# Orone-mini-S8H-v0r001.net
KiCad netlist of a schematic drawn in EAGLE
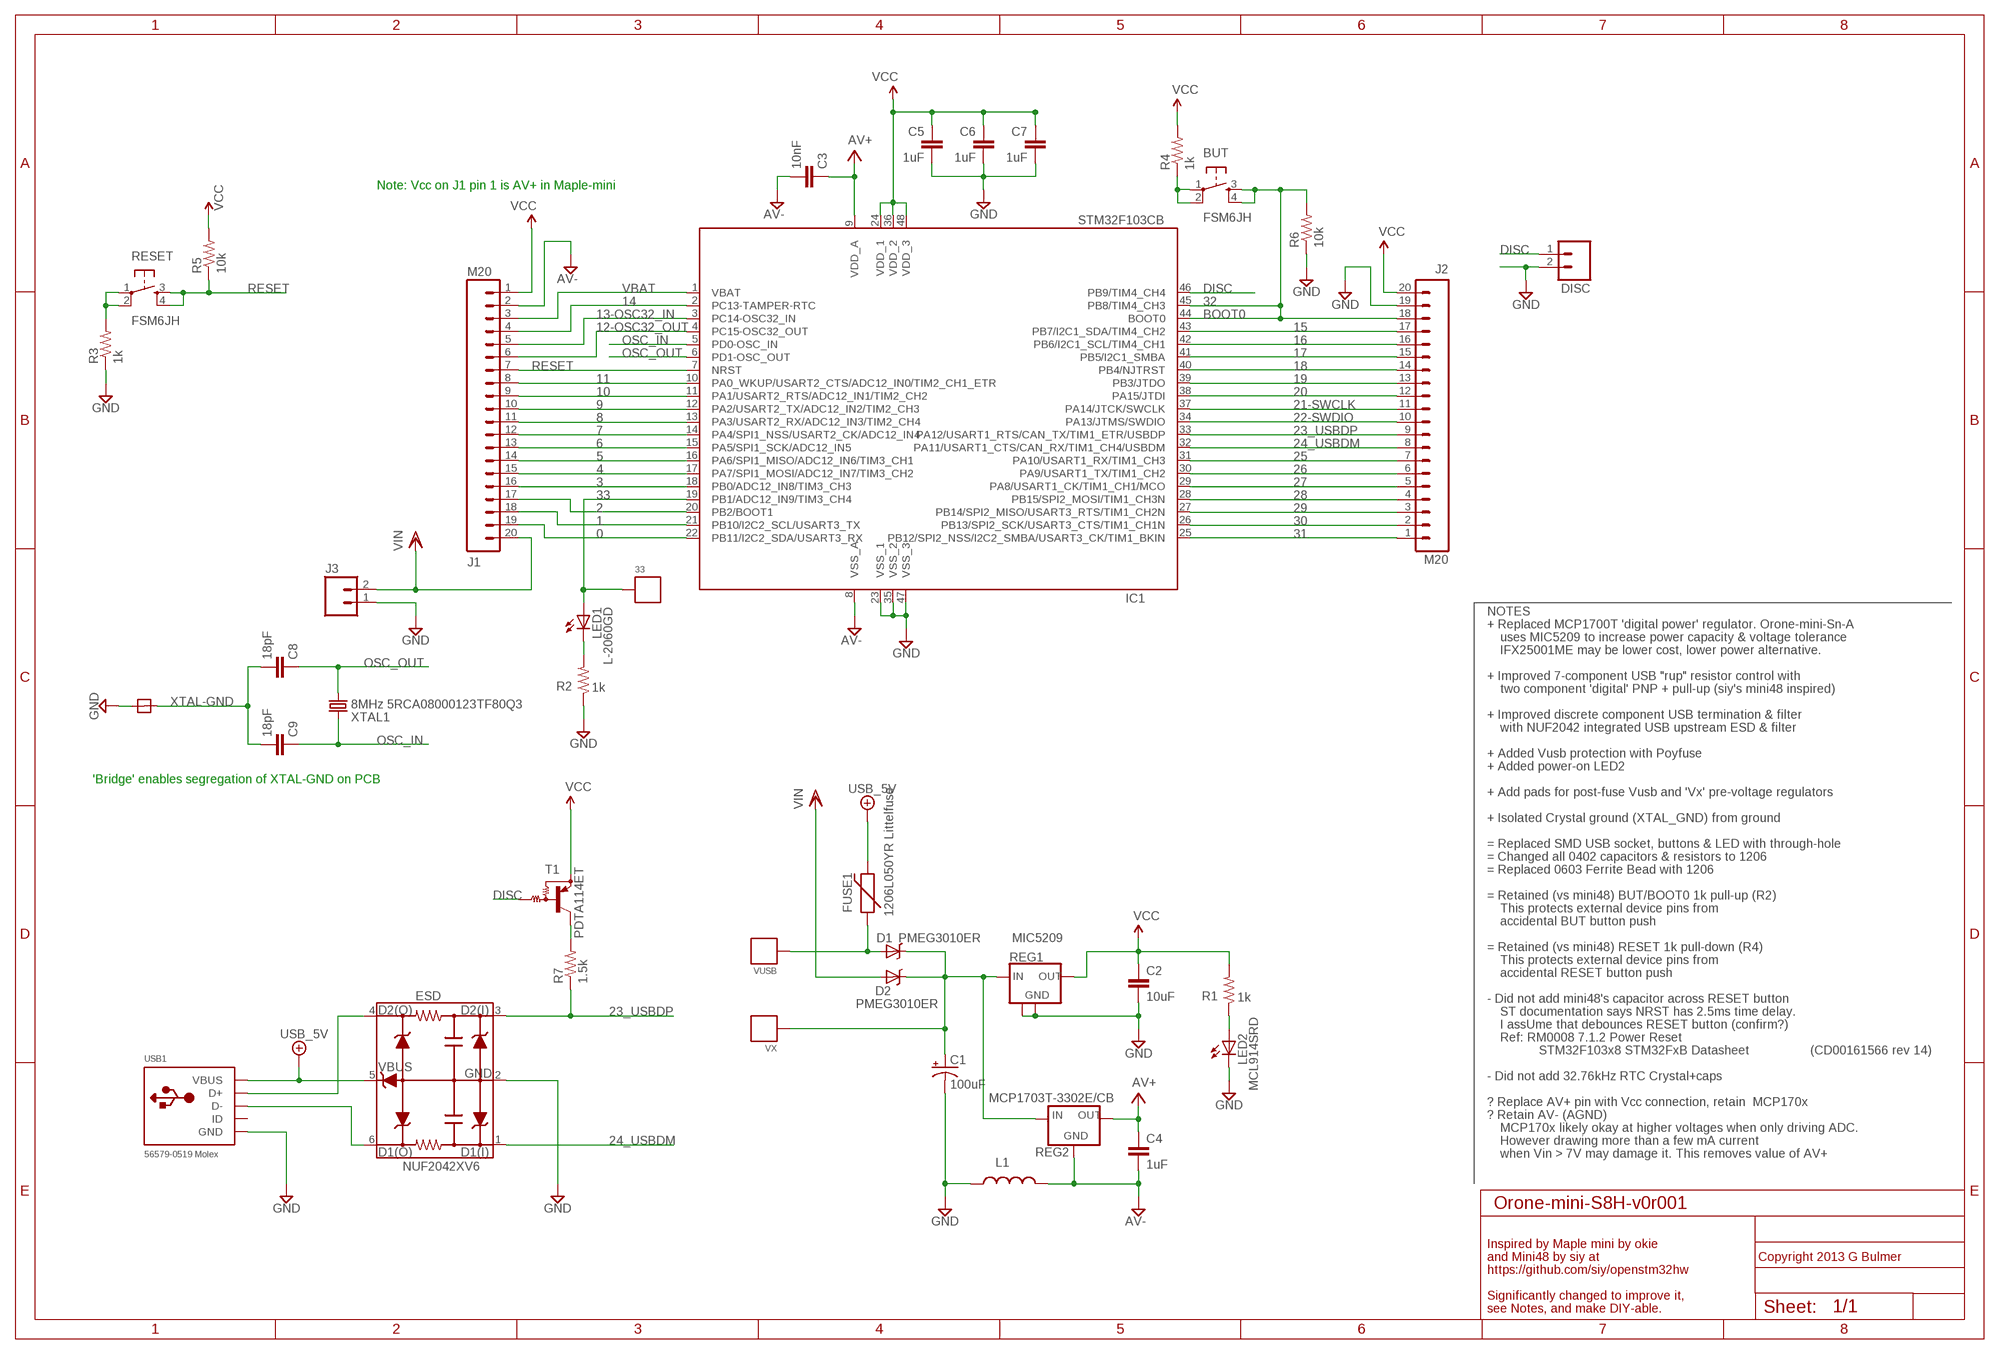
[diagram p0: schematic, sheet 1]

(export (version "E")
  (design (tool "Eeschema 10.0.6"))
  (components
    (comp (ref "33")
      (value "SIGNAL-PIN1")
      (footprint "eagle-import:1PIN")
      (libsource (lib "eagle-import") (part "SIGNAL-PIN1"))
    )
    (comp (ref "BUT")
      (value "FSM6JH")
      (footprint "eagle-import:TACTILE-PTH")
      (libsource (lib "eagle-import") (part "TAC_SWITCHPTH"))
    )
    (comp (ref "C1")
      (value "100uF")
      (footprint "eagle-import:EIA7343")
      (libsource (lib "eagle-import") (part "CAP_POL7343"))
    )
    (comp (ref "C2")
      (value "10uF")
      (footprint "eagle-import:1206")
      (libsource (lib "eagle-import") (part "CAP1206"))
    )
    (comp (ref "C3")
      (value "10nF")
      (footprint "eagle-import:1206")
      (libsource (lib "eagle-import") (part "CAP1206"))
    )
    (comp (ref "C4")
      (value "1uF")
      (footprint "eagle-import:1206")
      (libsource (lib "eagle-import") (part "CAP1206"))
    )
    (comp (ref "C5")
      (value "1uF")
      (footprint "eagle-import:1206")
      (libsource (lib "eagle-import") (part "CAP1206"))
    )
    (comp (ref "C6")
      (value "1uF")
      (footprint "eagle-import:1206")
      (libsource (lib "eagle-import") (part "CAP1206"))
    )
    (comp (ref "C7")
      (value "1uF")
      (footprint "eagle-import:1206")
      (libsource (lib "eagle-import") (part "CAP1206"))
    )
    (comp (ref "C8")
      (value "18pF")
      (footprint "eagle-import:1206")
      (libsource (lib "eagle-import") (part "CAP1206"))
    )
    (comp (ref "C9")
      (value "18pF")
      (footprint "eagle-import:1206")
      (libsource (lib "eagle-import") (part "CAP1206"))
    )
    (comp (ref "D1")
      (value "PMEG3010ER")
      (footprint "eagle-import:SOD-123W")
      (libsource (lib "eagle-import") (part "DIODE-SCHOTTKYSOD-123W"))
    )
    (comp (ref "D2")
      (value "PMEG3010ER")
      (footprint "eagle-import:SOD-123W")
      (libsource (lib "eagle-import") (part "DIODE-SCHOTTKYSOD-123W"))
    )
    (comp (ref "DISC")
      (value "M021X02_NO_SILK")
      (footprint "eagle-import:1X02_NO_SILK")
      (libsource (lib "eagle-import") (part "M021X02_NO_SILK"))
    )
    (comp (ref "ESD")
      (value "NUF2042XV6")
      (footprint "eagle-import:SOT563")
      (libsource (lib "eagle-import") (part "NUF2042XV6SOT563"))
    )
    (comp (ref "FUSE1")
      (value "1206L050YR Littelfuse")
      (footprint "eagle-import:PTC-1206")
      (libsource (lib "eagle-import") (part "PTCSMD"))
    )
    (comp (ref "IC1")
      (value "STM32F103CB")
      (footprint "eagle-import:LQFP48")
      (libsource (lib "eagle-import") (part "STM32F103CB"))
    )
    (comp (ref "J1")
      (value "M20")
      (footprint "eagle-import:1X20")
      (libsource (lib "eagle-import") (part "M20"))
    )
    (comp (ref "J2")
      (value "M20")
      (footprint "eagle-import:1X20")
      (libsource (lib "eagle-import") (part "M20"))
    )
    (comp (ref "J3")
      (value "M02POLAR")
      (footprint "eagle-import:MOLEX-1X2")
      (libsource (lib "eagle-import") (part "M02POLAR"))
    )
    (comp (ref "L1")
      (value "INDUCTOR1206")
      (footprint "eagle-import:1206")
      (libsource (lib "eagle-import") (part "INDUCTOR1206"))
    )
    (comp (ref "LED1")
      (value "L-2060GD")
      (footprint "eagle-import:LED1.8MM-1MM")
      (libsource (lib "eagle-import") (part "LED1.8MM-1MM"))
    )
    (comp (ref "LED2")
      (value "MCL914SRD")
      (footprint "eagle-import:LED1.8MM-1MM")
      (libsource (lib "eagle-import") (part "LED1.8MM-1MM"))
    )
    (comp (ref "R1")
      (value "1k")
      (footprint "eagle-import:1206")
      (libsource (lib "eagle-import") (part "RESISTOR1206"))
    )
    (comp (ref "R2")
      (value "1k")
      (footprint "eagle-import:1206")
      (libsource (lib "eagle-import") (part "RESISTOR1206"))
    )
    (comp (ref "R3")
      (value "1k")
      (footprint "eagle-import:1206")
      (libsource (lib "eagle-import") (part "RESISTOR1206"))
    )
    (comp (ref "R4")
      (value "1k")
      (footprint "eagle-import:1206")
      (libsource (lib "eagle-import") (part "RESISTOR1206"))
    )
    (comp (ref "R5")
      (value "10k")
      (footprint "eagle-import:1206")
      (libsource (lib "eagle-import") (part "RESISTOR1206"))
    )
    (comp (ref "R6")
      (value "10k")
      (footprint "eagle-import:1206")
      (libsource (lib "eagle-import") (part "RESISTOR1206"))
    )
    (comp (ref "R7")
      (value "1.5k")
      (footprint "eagle-import:1206")
      (libsource (lib "eagle-import") (part "RESISTOR1206"))
    )
    (comp (ref "REG1")
      (value "MIC5209")
      (footprint "eagle-import:SOT223-NT")
      (libsource (lib "eagle-import") (part "V_REG_LM2937SOT223-NT"))
    )
    (comp (ref "REG2")
      (value "MCP1703T-3302E/CB")
      (footprint "eagle-import:SOT23")
      (libsource (lib "eagle-import") (part "MCP170XSOT23"))
    )
    (comp (ref "RESET")
      (value "FSM6JH")
      (footprint "eagle-import:TACTILE-PTH")
      (libsource (lib "eagle-import") (part "TAC_SWITCHPTH"))
    )
    (comp (ref "T1")
      (value "PDTA114ET")
      (footprint "eagle-import:ES_SOT23-3")
      (libsource (lib "eagle-import") (part "ES_PNP-DRIVERSOT23-3"))
    )
    (comp (ref "U$4")
      (value "2PIN-GND-BRIDGE08X08MILS")
      (footprint "eagle-import:2PIN-08X08")
      (libsource (lib "eagle-import") (part "2PIN-GND-BRIDGE08X08MILS"))
    )
    (comp (ref "USB1")
      (value "56579-0519 Molex")
      (footprint "eagle-import:USB-MINI-AB-TH-MOLEX-DRILL")
      (libsource (lib "eagle-import") (part "USB-MINIBTH-DRILL"))
    )
    (comp (ref "VUSB")
      (value "SIGNAL-PIN1")
      (footprint "eagle-import:1PIN")
      (libsource (lib "eagle-import") (part "SIGNAL-PIN1"))
    )
    (comp (ref "VX")
      (value "SIGNAL-PIN1")
      (footprint "eagle-import:1PIN")
      (libsource (lib "eagle-import") (part "SIGNAL-PIN1"))
    )
    (comp (ref "XTAL1")
      (value "8MHz 5RCA08000123TF80Q3")
      (footprint "eagle-import:CRYSTAL-SMD-5X3")
      (libsource (lib "eagle-import") (part "CRYSTAL5X3"))
    )
  )
  (nets
    (net (code "1") (name "/0") (class "Default")
      (node (ref "IC1") (pin "22") (pinfunction "PB11/I2C2_SDA/USART3_RX_22") (pintype "input"))
      (node (ref "J1") (pin "19") (pinfunction "19_19") (pintype "passive"))
    )
    (net (code "2") (name "/1") (class "Default")
      (node (ref "IC1") (pin "21") (pinfunction "PB10/I2C2_SCL/USART3_TX_21") (pintype "input"))
      (node (ref "J1") (pin "18") (pinfunction "18_18") (pintype "passive"))
    )
    (net (code "3") (name "/2") (class "Default")
      (node (ref "IC1") (pin "20") (pinfunction "PB2/BOOT1_20") (pintype "bidirectional"))
      (node (ref "J1") (pin "17") (pinfunction "17_17") (pintype "passive"))
    )
    (net (code "4") (name "/3") (class "Default")
      (node (ref "IC1") (pin "18") (pinfunction "PB0/ADC12_IN8/TIM3_CH3_18") (pintype "bidirectional"))
      (node (ref "J1") (pin "16") (pinfunction "16_16") (pintype "passive"))
    )
    (net (code "5") (name "/4") (class "Default")
      (node (ref "IC1") (pin "17") (pinfunction "PA7/SPI1_MOSI/ADC12_IN7/TIM3_CH2_17") (pintype "bidirectional"))
      (node (ref "J1") (pin "15") (pinfunction "15_15") (pintype "passive"))
    )
    (net (code "6") (name "/5") (class "Default")
      (node (ref "IC1") (pin "16") (pinfunction "PA6/SPI1_MISO/ADC12_IN6/TIM3_CH1_16") (pintype "bidirectional"))
      (node (ref "J1") (pin "14") (pinfunction "14_14") (pintype "passive"))
    )
    (net (code "7") (name "/6") (class "Default")
      (node (ref "IC1") (pin "15") (pinfunction "PA5/SPI1_SCK/ADC12_IN5_15") (pintype "bidirectional"))
      (node (ref "J1") (pin "13") (pinfunction "13_13") (pintype "passive"))
    )
    (net (code "8") (name "/7") (class "Default")
      (node (ref "IC1") (pin "14") (pinfunction "PA4/SPI1_NSS/USART2_CK/ADC12_IN4_14") (pintype "bidirectional"))
      (node (ref "J1") (pin "12") (pinfunction "12_12") (pintype "passive"))
    )
    (net (code "9") (name "/8") (class "Default")
      (node (ref "IC1") (pin "13") (pinfunction "PA3/USART2_RX/ADC12_IN3/TIM2_CH4_13") (pintype "bidirectional"))
      (node (ref "J1") (pin "11") (pinfunction "11_11") (pintype "passive"))
    )
    (net (code "10") (name "/9") (class "Default")
      (node (ref "IC1") (pin "12") (pinfunction "PA2/USART2_TX/ADC12_IN2/TIM2_CH3_12") (pintype "bidirectional"))
      (node (ref "J1") (pin "10") (pinfunction "10_10") (pintype "passive"))
    )
    (net (code "11") (name "/10") (class "Default")
      (node (ref "IC1") (pin "11") (pinfunction "PA1/USART2_RTS/ADC12_IN1/TIM2_CH2_11") (pintype "bidirectional"))
      (node (ref "J1") (pin "9") (pinfunction "9_9") (pintype "passive"))
    )
    (net (code "12") (name "/11") (class "Default")
      (node (ref "IC1") (pin "10") (pinfunction "PA0_WKUP/USART2_CTS/ADC12_IN0/TIM2_CH1_ETR_10") (pintype "bidirectional"))
      (node (ref "J1") (pin "8") (pinfunction "8_8") (pintype "passive"))
    )
    (net (code "13") (name "/12-OSC32_OUT") (class "Default")
      (node (ref "IC1") (pin "4") (pinfunction "PC15-OSC32_OUT_4") (pintype "input"))
      (node (ref "J1") (pin "6") (pinfunction "6_6") (pintype "passive"))
    )
    (net (code "14") (name "/13-OSC32_IN") (class "Default")
      (node (ref "IC1") (pin "3") (pinfunction "PC14-OSC32_IN_3") (pintype "input"))
      (node (ref "J1") (pin "5") (pinfunction "5_5") (pintype "passive"))
    )
    (net (code "15") (name "/14") (class "Default")
      (node (ref "IC1") (pin "2") (pinfunction "PC13-TAMPER-RTC_2") (pintype "input"))
      (node (ref "J1") (pin "4") (pinfunction "4_4") (pintype "passive"))
    )
    (net (code "16") (name "/15") (class "Default")
      (node (ref "IC1") (pin "43") (pinfunction "PB7/I2C1_SDA/TIM4_CH2_43") (pintype "bidirectional"))
      (node (ref "J2") (pin "17") (pinfunction "17_17") (pintype "passive"))
    )
    (net (code "17") (name "/16") (class "Default")
      (node (ref "IC1") (pin "42") (pinfunction "PB6/I2C1_SCL/TIM4_CH1_42") (pintype "input"))
      (node (ref "J2") (pin "16") (pinfunction "16_16") (pintype "passive"))
    )
    (net (code "18") (name "/17") (class "Default")
      (node (ref "IC1") (pin "41") (pinfunction "PB5/I2C1_SMBA_41") (pintype "input"))
      (node (ref "J2") (pin "15") (pinfunction "15_15") (pintype "passive"))
    )
    (net (code "19") (name "/18") (class "Default")
      (node (ref "IC1") (pin "40") (pinfunction "PB4/NJTRST_40") (pintype "bidirectional"))
      (node (ref "J2") (pin "14") (pinfunction "14_14") (pintype "passive"))
    )
    (net (code "20") (name "/19") (class "Default")
      (node (ref "IC1") (pin "39") (pinfunction "PB3/JTDO_39") (pintype "bidirectional"))
      (node (ref "J2") (pin "13") (pinfunction "13_13") (pintype "passive"))
    )
    (net (code "21") (name "/20") (class "Default")
      (node (ref "IC1") (pin "38") (pinfunction "PA15/JTDI_38") (pintype "bidirectional"))
      (node (ref "J2") (pin "12") (pinfunction "12_12") (pintype "passive"))
    )
    (net (code "22") (name "/21-SWCLK") (class "Default")
      (node (ref "IC1") (pin "37") (pinfunction "PA14/JTCK/SWCLK_37") (pintype "bidirectional"))
      (node (ref "J2") (pin "11") (pinfunction "11_11") (pintype "passive"))
    )
    (net (code "23") (name "/22-SWDIO") (class "Default")
      (node (ref "IC1") (pin "34") (pinfunction "PA13/JTMS/SWDIO_34") (pintype "bidirectional"))
      (node (ref "J2") (pin "10") (pinfunction "10_10") (pintype "passive"))
    )
    (net (code "24") (name "/23_USBDP") (class "Default")
      (node (ref "ESD") (pin "3") (pinfunction "D2(I)_3") (pintype "bidirectional"))
      (node (ref "IC1") (pin "33") (pinfunction "PA12/USART1_RTS/CAN_TX/TIM1_ETR/USBDP_33") (pintype "bidirectional"))
      (node (ref "J2") (pin "9") (pinfunction "9_9") (pintype "passive"))
      (node (ref "R7") (pin "1") (pinfunction "1_1") (pintype "passive"))
    )
    (net (code "25") (name "/24_USBDM") (class "Default")
      (node (ref "ESD") (pin "1") (pinfunction "D1(I)_1") (pintype "bidirectional"))
      (node (ref "IC1") (pin "32") (pinfunction "PA11/USART1_CTS/CAN_RX/TIM1_CH4/USBDM_32") (pintype "bidirectional"))
      (node (ref "J2") (pin "8") (pinfunction "8_8") (pintype "passive"))
    )
    (net (code "26") (name "/25") (class "Default")
      (node (ref "IC1") (pin "31") (pinfunction "PA10/USART1_RX/TIM1_CH3_31") (pintype "bidirectional"))
      (node (ref "J2") (pin "7") (pinfunction "7_7") (pintype "passive"))
    )
    (net (code "27") (name "/26") (class "Default")
      (node (ref "IC1") (pin "30") (pinfunction "PA9/USART1_TX/TIM1_CH2_30") (pintype "input"))
      (node (ref "J2") (pin "6") (pinfunction "6_6") (pintype "passive"))
    )
    (net (code "28") (name "/27") (class "Default")
      (node (ref "IC1") (pin "29") (pinfunction "PA8/USART1_CK/TIM1_CH1/MCO_29") (pintype "bidirectional"))
      (node (ref "J2") (pin "5") (pinfunction "5_5") (pintype "passive"))
    )
    (net (code "29") (name "/28") (class "Default")
      (node (ref "IC1") (pin "28") (pinfunction "PB15/SPI2_MOSI/TIM1_CH3N_28") (pintype "input"))
      (node (ref "J2") (pin "4") (pinfunction "4_4") (pintype "passive"))
    )
    (net (code "30") (name "/29") (class "Default")
      (node (ref "IC1") (pin "27") (pinfunction "PB14/SPI2_MISO/USART3_RTS/TIM1_CH2N_27") (pintype "input"))
      (node (ref "J2") (pin "3") (pinfunction "3_3") (pintype "passive"))
    )
    (net (code "31") (name "/30") (class "Default")
      (node (ref "IC1") (pin "26") (pinfunction "PB13/SPI2_SCK/USART3_CTS/TIM1_CH1N_26") (pintype "input"))
      (node (ref "J2") (pin "2") (pinfunction "2_2") (pintype "passive"))
    )
    (net (code "32") (name "/31") (class "Default")
      (node (ref "IC1") (pin "25") (pinfunction "PB12/SPI2_NSS/I2C2_SMBA/USART3_CK/TIM1_BKIN_25") (pintype "input"))
      (node (ref "J2") (pin "1") (pinfunction "1_1") (pintype "passive"))
    )
    (net (code "33") (name "/32") (class "Default")
      (node (ref "BUT") (pin "3") (pinfunction "3_3") (pintype "passive"))
      (node (ref "BUT") (pin "4") (pinfunction "4_4") (pintype "passive"))
      (node (ref "IC1") (pin "44") (pinfunction "BOOT0_44") (pintype "input"))
      (node (ref "IC1") (pin "45") (pinfunction "PB8/TIM4_CH3_45") (pintype "bidirectional"))
      (node (ref "J2") (pin "18") (pinfunction "18_18") (pintype "passive"))
      (node (ref "R6") (pin "2") (pinfunction "2_2") (pintype "passive"))
    )
    (net (code "34") (name "/33") (class "Default")
      (node (ref "33") (pin "P$1") (pinfunction "P$1_P$1") (pintype "bidirectional"))
      (node (ref "IC1") (pin "19") (pinfunction "PB1/ADC12_IN9/TIM3_CH4_19") (pintype "bidirectional"))
      (node (ref "LED1") (pin "A") (pinfunction "A_A") (pintype "passive"))
    )
    (net (code "35") (name "/DISC") (class "Default")
      (node (ref "DISC") (pin "1") (pinfunction "1_1") (pintype "passive"))
      (node (ref "IC1") (pin "46") (pinfunction "PB9/TIM4_CH4_46") (pintype "input"))
      (node (ref "T1") (pin "1") (pinfunction "B_1") (pintype "passive"))
    )
    (net (code "36") (name "/OSC_IN") (class "Default")
      (node (ref "C9") (pin "1") (pinfunction "1_1") (pintype "passive"))
      (node (ref "IC1") (pin "5") (pinfunction "PD0-OSC_IN_5") (pintype "input"))
      (node (ref "XTAL1") (pin "3") (pinfunction "2_3") (pintype "passive"))
    )
    (net (code "37") (name "/OSC_OUT") (class "Default")
      (node (ref "C8") (pin "1") (pinfunction "1_1") (pintype "passive"))
      (node (ref "IC1") (pin "6") (pinfunction "PD1-OSC_OUT_6") (pintype "input"))
      (node (ref "XTAL1") (pin "1") (pinfunction "1_1") (pintype "passive"))
    )
    (net (code "38") (name "/RESET") (class "Default")
      (node (ref "IC1") (pin "7") (pinfunction "NRST_7") (pintype "input"))
      (node (ref "J1") (pin "7") (pinfunction "7_7") (pintype "passive"))
      (node (ref "R5") (pin "1") (pinfunction "1_1") (pintype "passive"))
      (node (ref "RESET") (pin "3") (pinfunction "3_3") (pintype "passive"))
      (node (ref "RESET") (pin "4") (pinfunction "4_4") (pintype "passive"))
    )
    (net (code "39") (name "/VBAT") (class "Default")
      (node (ref "IC1") (pin "1") (pinfunction "VBAT_1") (pintype "power_in"))
      (node (ref "J1") (pin "3") (pinfunction "3_3") (pintype "passive"))
    )
    (net (code "40") (name "/XTAL-GND") (class "Default")
      (node (ref "C8") (pin "2") (pinfunction "2_2") (pintype "passive"))
      (node (ref "C9") (pin "2") (pinfunction "2_2") (pintype "passive"))
      (node (ref "U$4") (pin "P$2") (pinfunction "P$2_P$2") (pintype "bidirectional"))
    )
    (net (code "41") (name "AV+") (class "Default")
      (node (ref "C3") (pin "1") (pinfunction "1_1") (pintype "passive"))
      (node (ref "C4") (pin "1") (pinfunction "1_1") (pintype "passive"))
      (node (ref "IC1") (pin "9") (pinfunction "VDD_A_9") (pintype "power_in"))
      (node (ref "REG2") (pin "2") (pinfunction "OUT_2") (pintype "power_in"))
    )
    (net (code "42") (name "AV-") (class "Default")
      (node (ref "C3") (pin "2") (pinfunction "2_2") (pintype "passive"))
      (node (ref "C4") (pin "2") (pinfunction "2_2") (pintype "passive"))
      (node (ref "IC1") (pin "8") (pinfunction "VSS_A_8") (pintype "power_in"))
      (node (ref "J1") (pin "2") (pinfunction "2_2") (pintype "passive"))
      (node (ref "L1") (pin "2") (pinfunction "2_2") (pintype "passive"))
      (node (ref "REG2") (pin "1") (pinfunction "GND_1") (pintype "power_in"))
    )
    (net (code "43") (name "GND") (class "Default")
      (node (ref "C1") (pin "C") (pinfunction "-_C") (pintype "passive"))
      (node (ref "C2") (pin "2") (pinfunction "2_2") (pintype "passive"))
      (node (ref "C5") (pin "2") (pinfunction "2_2") (pintype "passive"))
      (node (ref "C6") (pin "2") (pinfunction "2_2") (pintype "passive"))
      (node (ref "C7") (pin "2") (pinfunction "2_2") (pintype "passive"))
      (node (ref "DISC") (pin "2") (pinfunction "2_2") (pintype "passive"))
      (node (ref "ESD") (pin "2") (pinfunction "GND_2") (pintype "bidirectional"))
      (node (ref "IC1") (pin "23") (pinfunction "VSS_1_23") (pintype "power_in"))
      (node (ref "IC1") (pin "35") (pinfunction "VSS_2_35") (pintype "power_in"))
      (node (ref "IC1") (pin "47") (pinfunction "VSS_3_47") (pintype "power_in"))
      (node (ref "J2") (pin "19") (pinfunction "19_19") (pintype "passive"))
      (node (ref "J3") (pin "1") (pinfunction "1_1") (pintype "passive"))
      (node (ref "L1") (pin "1") (pinfunction "1_1") (pintype "passive"))
      (node (ref "LED2") (pin "C") (pinfunction "C_C") (pintype "passive"))
      (node (ref "R2") (pin "1") (pinfunction "1_1") (pintype "passive"))
      (node (ref "R3") (pin "1") (pinfunction "1_1") (pintype "passive"))
      (node (ref "R6") (pin "1") (pinfunction "1_1") (pintype "passive"))
      (node (ref "REG1") (pin "2") (pinfunction "GND_2") (pintype "power_in"))
      (node (ref "REG1") (pin "4") (pinfunction "GND_4") (pintype "power_in"))
      (node (ref "U$4") (pin "P$1") (pinfunction "P$1_P$1") (pintype "bidirectional"))
      (node (ref "USB1") (pin "GND") (pinfunction "GND_GND") (pintype "power_in"))
    )
    (net (code "44") (name "Net-(BUT-Pad1)") (class "Default")
      (node (ref "BUT") (pin "1") (pinfunction "1_1") (pintype "passive"))
      (node (ref "BUT") (pin "2") (pinfunction "2_2") (pintype "passive"))
      (node (ref "R4") (pin "1") (pinfunction "1_1") (pintype "passive"))
    )
    (net (code "45") (name "Net-(C1-+)") (class "Default")
      (node (ref "C1") (pin "A") (pinfunction "+_A") (pintype "passive"))
      (node (ref "D1") (pin "P$1.CATHODE") (pinfunction "C_P$1.CATHODE") (pintype "passive"))
      (node (ref "D2") (pin "P$1.CATHODE") (pinfunction "C_P$1.CATHODE") (pintype "passive"))
      (node (ref "REG1") (pin "1") (pinfunction "IN_1") (pintype "power_in"))
      (node (ref "REG2") (pin "3") (pinfunction "IN_3") (pintype "input"))
      (node (ref "VX") (pin "P$1") (pinfunction "P$1_P$1") (pintype "bidirectional"))
    )
    (net (code "46") (name "Net-(D1-A)") (class "Default")
      (node (ref "D1") (pin "P$2.ANODE") (pinfunction "A_P$2.ANODE") (pintype "passive"))
      (node (ref "FUSE1") (pin "1") (pinfunction "1_1") (pintype "bidirectional"))
      (node (ref "VUSB") (pin "P$1") (pinfunction "P$1_P$1") (pintype "bidirectional"))
    )
    (net (code "47") (name "Net-(ESD-D1(O))") (class "Default")
      (node (ref "ESD") (pin "6") (pinfunction "D1(O)_6") (pintype "bidirectional"))
      (node (ref "USB1") (pin "D-") (pinfunction "D-_D-") (pintype "bidirectional"))
    )
    (net (code "48") (name "Net-(ESD-D2(O))") (class "Default")
      (node (ref "ESD") (pin "4") (pinfunction "D2(O)_4") (pintype "bidirectional"))
      (node (ref "USB1") (pin "D+") (pinfunction "D+_D+") (pintype "bidirectional"))
    )
    (net (code "49") (name "Net-(LED1-PadC)") (class "Default")
      (node (ref "LED1") (pin "C") (pinfunction "C_C") (pintype "passive"))
      (node (ref "R2") (pin "2") (pinfunction "2_2") (pintype "passive"))
    )
    (net (code "50") (name "Net-(LED2-PadA)") (class "Default")
      (node (ref "LED2") (pin "A") (pinfunction "A_A") (pintype "passive"))
      (node (ref "R1") (pin "1") (pinfunction "1_1") (pintype "passive"))
    )
    (net (code "51") (name "Net-(R3-Pad2)") (class "Default")
      (node (ref "R3") (pin "2") (pinfunction "2_2") (pintype "passive"))
      (node (ref "RESET") (pin "1") (pinfunction "1_1") (pintype "passive"))
      (node (ref "RESET") (pin "2") (pinfunction "2_2") (pintype "passive"))
    )
    (net (code "52") (name "Net-(T1-C)") (class "Default")
      (node (ref "R7") (pin "2") (pinfunction "2_2") (pintype "passive"))
      (node (ref "T1") (pin "3") (pinfunction "C_3") (pintype "passive"))
    )
    (net (code "53") (name "USB_5V") (class "Default")
      (node (ref "ESD") (pin "5") (pinfunction "VBUS_5") (pintype "bidirectional"))
      (node (ref "FUSE1") (pin "2") (pinfunction "2_2") (pintype "bidirectional"))
      (node (ref "USB1") (pin "VBUS") (pinfunction "VBUS_VBUS") (pintype "power_in"))
    )
    (net (code "54") (name "VCC") (class "Default")
      (node (ref "C2") (pin "1") (pinfunction "1_1") (pintype "passive"))
      (node (ref "C5") (pin "1") (pinfunction "1_1") (pintype "passive"))
      (node (ref "C6") (pin "1") (pinfunction "1_1") (pintype "passive"))
      (node (ref "C7") (pin "1") (pinfunction "1_1") (pintype "passive"))
      (node (ref "IC1") (pin "24") (pinfunction "VDD_1_24") (pintype "power_in"))
      (node (ref "IC1") (pin "36") (pinfunction "VDD_2_36") (pintype "power_in"))
      (node (ref "IC1") (pin "48") (pinfunction "VDD_3_48") (pintype "power_in"))
      (node (ref "J1") (pin "1") (pinfunction "1_1") (pintype "passive"))
      (node (ref "J2") (pin "20") (pinfunction "20_20") (pintype "passive"))
      (node (ref "R1") (pin "2") (pinfunction "2_2") (pintype "passive"))
      (node (ref "R4") (pin "2") (pinfunction "2_2") (pintype "passive"))
      (node (ref "R5") (pin "2") (pinfunction "2_2") (pintype "passive"))
      (node (ref "REG1") (pin "3") (pinfunction "OUT_3") (pintype "power_in"))
      (node (ref "T1") (pin "2") (pinfunction "E_2") (pintype "passive"))
    )
    (net (code "55") (name "VIN") (class "Default")
      (node (ref "D2") (pin "P$2.ANODE") (pinfunction "A_P$2.ANODE") (pintype "passive"))
      (node (ref "J1") (pin "20") (pinfunction "20_20") (pintype "passive"))
      (node (ref "J3") (pin "2") (pinfunction "2_2") (pintype "passive"))
    )
    (net (code "56") (name "unconnected-(USB1-PadID)") (class "Default")
      (node (ref "USB1") (pin "ID") (pinfunction "ID_ID") (pintype "bidirectional"))
    )
  )
)
